# Connecors.net
KiCad netlist of a schematic drawn in Altium Designer
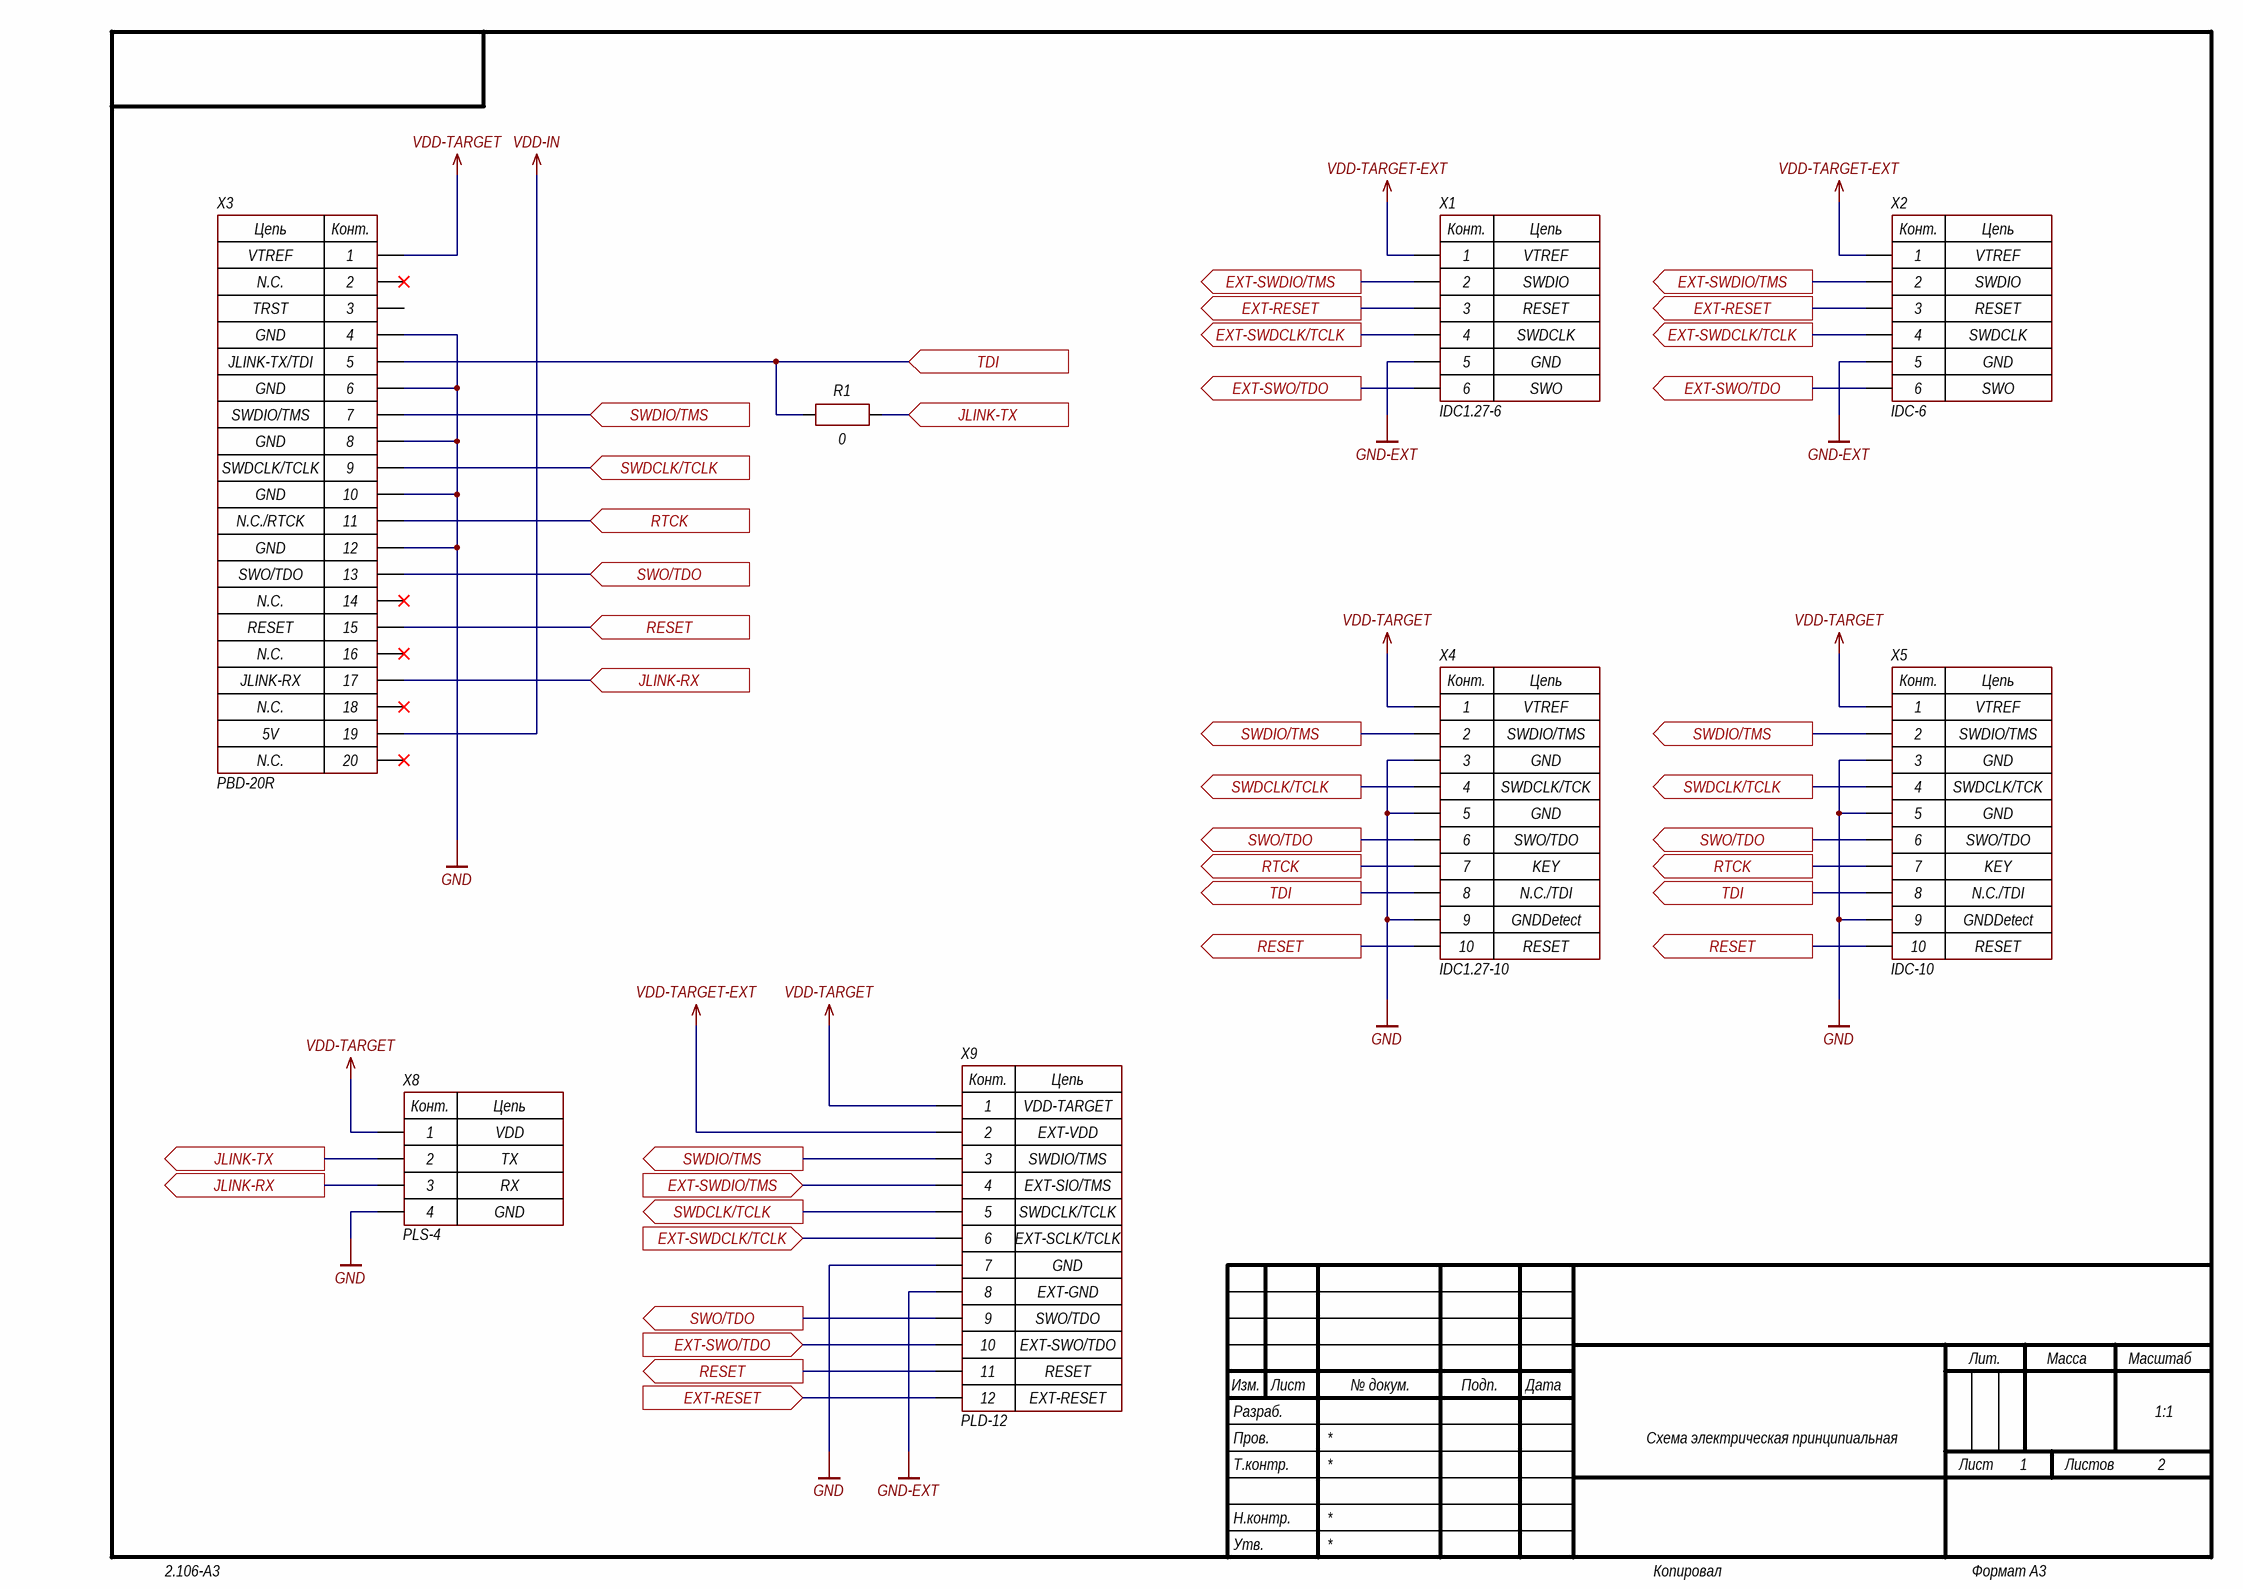
[diagram p0: Connecors.SchDoc]

(export (version "E")
  (design (tool "Eeschema 10.0.6"))
  (components
    (comp (ref "R1") (value "0") (footprint "CH0402R") (libsource (lib "Discrete") (part "Resistor")))
    (comp (ref "X1")
      (value "IDC1.27-6")
      (footprint "CON: IDC1.27-6")
      (libsource (lib "Connectors") (part "6-Connector"))
    )
    (comp (ref "X2")
      (value "IDC-6")
      (footprint "custom:CON: IDC-6MS")
      (libsource (lib "Connectors") (part "6-Connector"))
    )
    (comp (ref "X3")
      (value "PBD-20R")
      (footprint "CON: PBD-20R")
      (libsource (lib "Connectors") (part "20-Connector"))
    )
    (comp (ref "X4")
      (value "IDC1.27-10")
      (footprint "CON: IDC1.27-10")
      (libsource (lib "Connectors") (part "10-Connector"))
    )
    (comp (ref "X5")
      (value "IDC-10")
      (footprint "CON: IDC-10MS")
      (libsource (lib "Connectors") (part "10-Connector"))
    )
    (comp (ref "X8")
      (value "PLS-4")
      (footprint "CON: PLS-4")
      (libsource (lib "Connectors") (part "4-Connector"))
    )
    (comp (ref "X9")
      (value "PLD-12")
      (footprint "CON: PLD-12")
      (libsource (lib "Connectors") (part "12-Connector"))
    )
  )
  (nets
    (net (code "1") (name "/EXT-RESET") (class "Default")
      (node (ref "X1") (pin "3") (pinfunction "3_3") (pintype "passive"))
      (node (ref "X2") (pin "3") (pinfunction "3_3") (pintype "passive"))
      (node (ref "X9") (pin "12") (pinfunction "12_12") (pintype "passive"))
    )
    (net (code "2") (name "/EXT-SWDCLK{slash}TCLK") (class "Default")
      (node (ref "X1") (pin "4") (pinfunction "4_4") (pintype "passive"))
      (node (ref "X2") (pin "4") (pinfunction "4_4") (pintype "passive"))
      (node (ref "X9") (pin "6") (pinfunction "6_6") (pintype "passive"))
    )
    (net (code "3") (name "/EXT-SWDIO{slash}TMS") (class "Default")
      (node (ref "X1") (pin "2") (pinfunction "2_2") (pintype "passive"))
      (node (ref "X2") (pin "2") (pinfunction "2_2") (pintype "passive"))
      (node (ref "X9") (pin "4") (pinfunction "4_4") (pintype "passive"))
    )
    (net (code "4") (name "/EXT-SWO{slash}TDO") (class "Default")
      (node (ref "X1") (pin "6") (pinfunction "6_6") (pintype "passive"))
      (node (ref "X2") (pin "6") (pinfunction "6_6") (pintype "passive"))
      (node (ref "X9") (pin "10") (pinfunction "10_10") (pintype "passive"))
    )
    (net (code "5") (name "/JLINK-RX") (class "Default")
      (node (ref "X3") (pin "17") (pinfunction "17_17") (pintype "passive"))
      (node (ref "X8") (pin "3") (pinfunction "3_3") (pintype "passive"))
    )
    (net (code "6") (name "/JLINK-TX") (class "Default")
      (node (ref "R1") (pin "2") (pinfunction "2_2") (pintype "passive"))
      (node (ref "X8") (pin "2") (pinfunction "2_2") (pintype "passive"))
    )
    (net (code "7") (name "/RESET") (class "Default")
      (node (ref "X3") (pin "15") (pinfunction "15_15") (pintype "passive"))
      (node (ref "X4") (pin "10") (pinfunction "10_10") (pintype "passive"))
      (node (ref "X5") (pin "10") (pinfunction "10_10") (pintype "passive"))
      (node (ref "X9") (pin "11") (pinfunction "11_11") (pintype "passive"))
    )
    (net (code "8") (name "/RTCK") (class "Default")
      (node (ref "X3") (pin "11") (pinfunction "11_11") (pintype "passive"))
      (node (ref "X4") (pin "7") (pinfunction "7_7") (pintype "passive"))
      (node (ref "X5") (pin "7") (pinfunction "7_7") (pintype "passive"))
    )
    (net (code "9") (name "/SWDCLK{slash}TCLK") (class "Default")
      (node (ref "X3") (pin "9") (pinfunction "9_9") (pintype "passive"))
      (node (ref "X4") (pin "4") (pinfunction "4_4") (pintype "passive"))
      (node (ref "X5") (pin "4") (pinfunction "4_4") (pintype "passive"))
      (node (ref "X9") (pin "5") (pinfunction "5_5") (pintype "passive"))
    )
    (net (code "10") (name "/SWDIO{slash}TMS") (class "Default")
      (node (ref "X3") (pin "7") (pinfunction "7_7") (pintype "passive"))
      (node (ref "X4") (pin "2") (pinfunction "2_2") (pintype "passive"))
      (node (ref "X5") (pin "2") (pinfunction "2_2") (pintype "passive"))
      (node (ref "X9") (pin "3") (pinfunction "3_3") (pintype "passive"))
    )
    (net (code "11") (name "/SWO{slash}TDO") (class "Default")
      (node (ref "X3") (pin "13") (pinfunction "13_13") (pintype "passive"))
      (node (ref "X4") (pin "6") (pinfunction "6_6") (pintype "passive"))
      (node (ref "X5") (pin "6") (pinfunction "6_6") (pintype "passive"))
      (node (ref "X9") (pin "9") (pinfunction "9_9") (pintype "passive"))
    )
    (net (code "12") (name "/TDI") (class "Default")
      (node (ref "R1") (pin "1") (pinfunction "1_1") (pintype "passive"))
      (node (ref "X3") (pin "5") (pinfunction "5_5") (pintype "passive"))
      (node (ref "X4") (pin "8") (pinfunction "8_8") (pintype "passive"))
      (node (ref "X5") (pin "8") (pinfunction "8_8") (pintype "passive"))
    )
    (net (code "13") (name "GND") (class "Default")
      (node (ref "X3") (pin "10") (pinfunction "10_10") (pintype "passive"))
      (node (ref "X3") (pin "12") (pinfunction "12_12") (pintype "passive"))
      (node (ref "X3") (pin "4") (pinfunction "4_4") (pintype "passive"))
      (node (ref "X3") (pin "6") (pinfunction "6_6") (pintype "passive"))
      (node (ref "X3") (pin "8") (pinfunction "8_8") (pintype "passive"))
      (node (ref "X4") (pin "3") (pinfunction "3_3") (pintype "passive"))
      (node (ref "X4") (pin "5") (pinfunction "5_5") (pintype "passive"))
      (node (ref "X4") (pin "9") (pinfunction "9_9") (pintype "passive"))
      (node (ref "X5") (pin "3") (pinfunction "3_3") (pintype "passive"))
      (node (ref "X5") (pin "5") (pinfunction "5_5") (pintype "passive"))
      (node (ref "X5") (pin "9") (pinfunction "9_9") (pintype "passive"))
      (node (ref "X8") (pin "4") (pinfunction "4_4") (pintype "passive"))
      (node (ref "X9") (pin "7") (pinfunction "7_7") (pintype "passive"))
    )
    (net (code "14") (name "GND-EXT") (class "Default")
      (node (ref "X1") (pin "5") (pinfunction "5_5") (pintype "passive"))
      (node (ref "X2") (pin "5") (pinfunction "5_5") (pintype "passive"))
      (node (ref "X9") (pin "8") (pinfunction "8_8") (pintype "passive"))
    )
    (net (code "15") (name "VDD-IN") (class "Default")
      (node (ref "X3") (pin "19") (pinfunction "19_19") (pintype "passive"))
    )
    (net (code "16") (name "VDD-TARGET") (class "Default")
      (node (ref "X3") (pin "1") (pinfunction "1_1") (pintype "passive"))
      (node (ref "X4") (pin "1") (pinfunction "1_1") (pintype "passive"))
      (node (ref "X5") (pin "1") (pinfunction "1_1") (pintype "passive"))
      (node (ref "X8") (pin "1") (pinfunction "1_1") (pintype "passive"))
      (node (ref "X9") (pin "1") (pinfunction "1_1") (pintype "passive"))
    )
    (net (code "17") (name "VDD-TARGET-EXT") (class "Default")
      (node (ref "X1") (pin "1") (pinfunction "1_1") (pintype "passive"))
      (node (ref "X2") (pin "1") (pinfunction "1_1") (pintype "passive"))
      (node (ref "X9") (pin "2") (pinfunction "2_2") (pintype "passive"))
    )
    (net (code "18") (name "unconnected-(X3-Pad2)") (class "Default")
      (node (ref "X3") (pin "2") (pinfunction "2_2") (pintype "passive+no_connect"))
    )
    (net (code "19") (name "unconnected-(X3-Pad3)") (class "Default")
      (node (ref "X3") (pin "3") (pinfunction "3_3") (pintype "passive"))
    )
    (net (code "20") (name "unconnected-(X3-Pad14)") (class "Default")
      (node (ref "X3") (pin "14") (pinfunction "14_14") (pintype "passive+no_connect"))
    )
    (net (code "21") (name "unconnected-(X3-Pad16)") (class "Default")
      (node (ref "X3") (pin "16") (pinfunction "16_16") (pintype "passive+no_connect"))
    )
    (net (code "22") (name "unconnected-(X3-Pad18)") (class "Default")
      (node (ref "X3") (pin "18") (pinfunction "18_18") (pintype "passive+no_connect"))
    )
    (net (code "23") (name "unconnected-(X3-Pad20)") (class "Default")
      (node (ref "X3") (pin "20") (pinfunction "20_20") (pintype "passive+no_connect"))
    )
  )
)
